# BME_board-v1-6.net
KiCad netlist of a schematic drawn in EAGLE
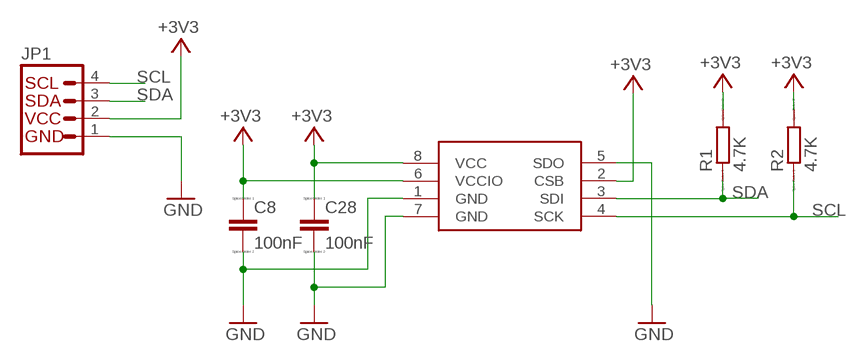
[diagram p0: schematic, sheet 1]

(export (version "E")
  (design (tool "Eeschema 10.0.6"))
  (components
    (comp (ref "C8")
      (value "100nF")
      (footprint "eagle-import:C0603")
      (libsource (lib "eagle-import") (part "CC0603"))
    )
    (comp (ref "C28")
      (value "100nF")
      (footprint "eagle-import:C0603")
      (libsource (lib "eagle-import") (part "CC0603"))
    )
    (comp (ref "IC2")
      (value "BME280")
      (footprint "eagle-import:BME280")
      (libsource (lib "eagle-import") (part "BME280"))
    )
    (comp (ref "JP1")
      (value "I2C_STANDARD")
      (footprint "eagle-import:1X04")
      (libsource (lib "eagle-import") (part "I2C_STANDARD"))
    )
    (comp (ref "R1")
      (value "4.7K")
      (footprint "eagle-import:R0603")
      (libsource (lib "eagle-import") (part "RR0603"))
    )
    (comp (ref "R2")
      (value "4.7K")
      (footprint "eagle-import:R0603")
      (libsource (lib "eagle-import") (part "RR0603"))
    )
  )
  (nets
    (net (code "1") (name "+3V3") (class "Default")
      (node (ref "C28") (pin "1") (pinfunction "1_1") (pintype "passive"))
      (node (ref "C8") (pin "1") (pinfunction "1_1") (pintype "passive"))
      (node (ref "IC2") (pin "2") (pinfunction "CSB_2") (pintype "bidirectional"))
      (node (ref "IC2") (pin "6") (pinfunction "VCCIO_6") (pintype "bidirectional"))
      (node (ref "IC2") (pin "8") (pinfunction "VCC_8") (pintype "bidirectional"))
      (node (ref "JP1") (pin "2") (pinfunction "2_2") (pintype "passive"))
      (node (ref "R1") (pin "2") (pinfunction "2_2") (pintype "passive"))
      (node (ref "R2") (pin "2") (pinfunction "2_2") (pintype "passive"))
    )
    (net (code "2") (name "/SCL") (class "Default")
      (node (ref "IC2") (pin "4") (pinfunction "SCK_4") (pintype "bidirectional"))
      (node (ref "JP1") (pin "4") (pinfunction "4_4") (pintype "passive"))
      (node (ref "R2") (pin "1") (pinfunction "1_1") (pintype "passive"))
    )
    (net (code "3") (name "/SDA") (class "Default")
      (node (ref "IC2") (pin "3") (pinfunction "SDI_3") (pintype "bidirectional"))
      (node (ref "JP1") (pin "3") (pinfunction "3_3") (pintype "passive"))
      (node (ref "R1") (pin "1") (pinfunction "1_1") (pintype "passive"))
    )
    (net (code "4") (name "GND") (class "Default")
      (node (ref "C28") (pin "2") (pinfunction "2_2") (pintype "passive"))
      (node (ref "C8") (pin "2") (pinfunction "2_2") (pintype "passive"))
      (node (ref "IC2") (pin "1") (pinfunction "GND_1") (pintype "bidirectional"))
      (node (ref "IC2") (pin "5") (pinfunction "SDO_5") (pintype "bidirectional"))
      (node (ref "IC2") (pin "7") (pinfunction "GND_7") (pintype "bidirectional"))
      (node (ref "JP1") (pin "1") (pinfunction "1_1") (pintype "passive"))
    )
  )
)
